# Motion_sensor.net
KiCad netlist of a schematic drawn in Altium Designer
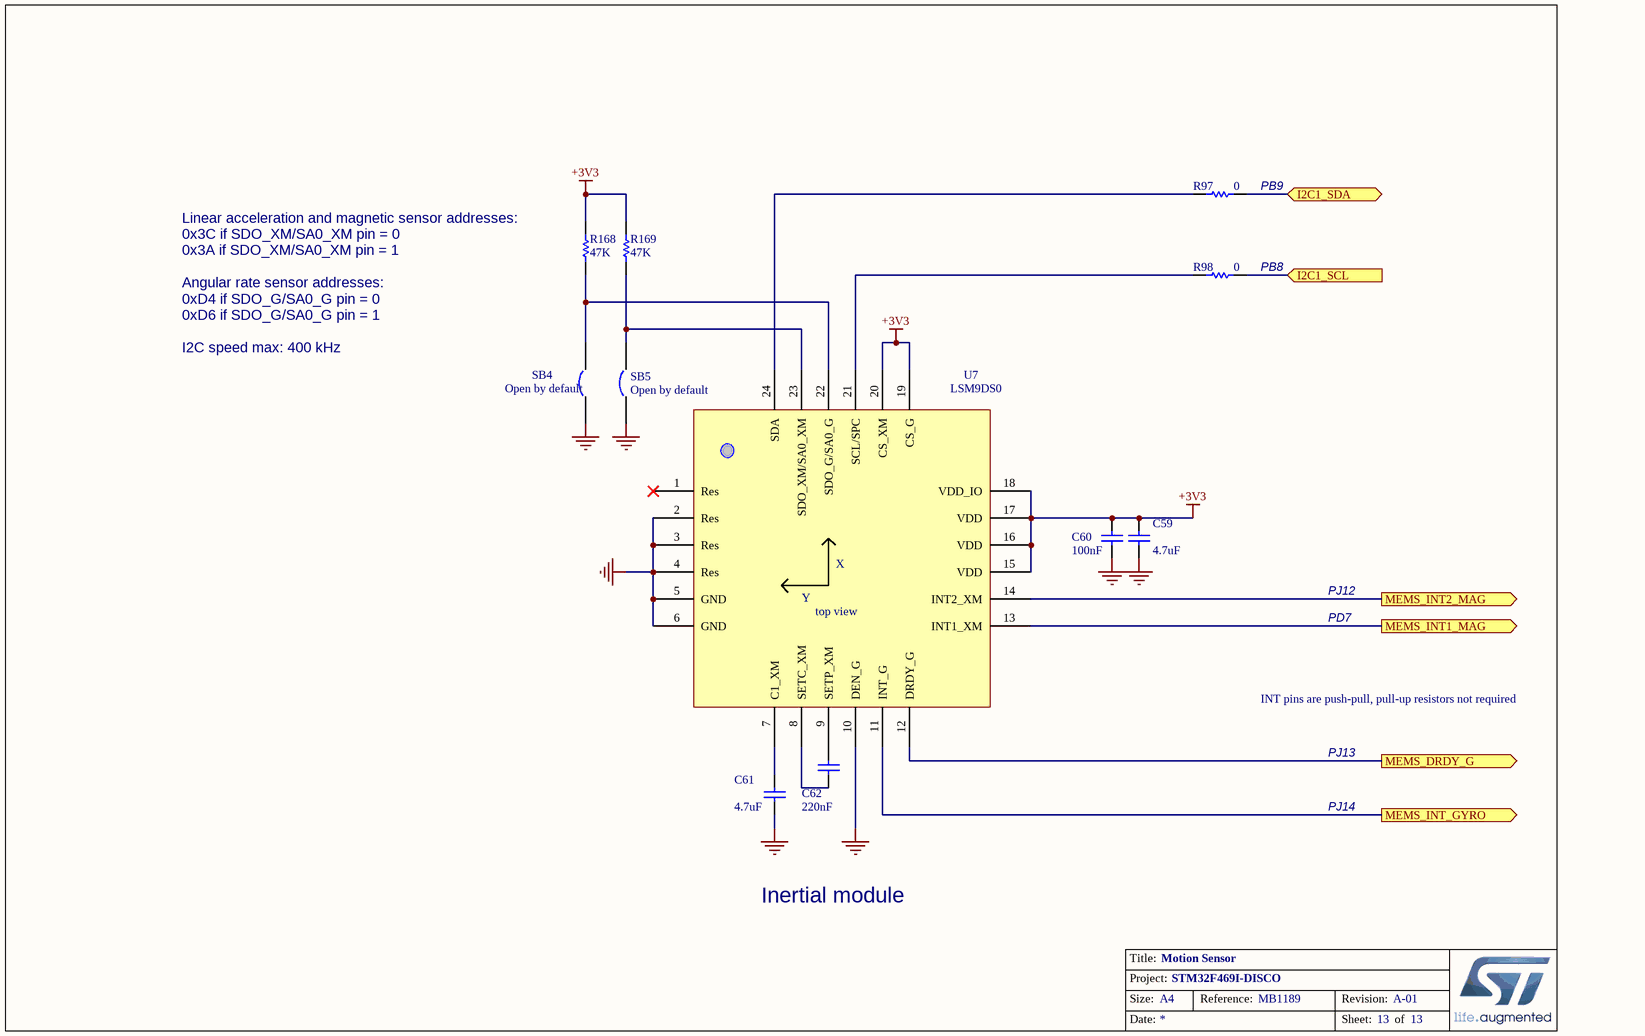
[diagram p0: Motion_sensor.SchDoc]

(export (version "E")
  (design (tool "Eeschema 10.0.6"))
  (components
    (comp (ref "C59")
      (value "4.7uF")
      (footprint "0603C")
      (description "Capacitor")
      (fields (field (name "PUBLISHER") "Altium Limited"))
      (libsource (lib "Miscellaneous Devices") (part "Cap"))
    )
    (comp (ref "C60")
      (value "100nF")
      (footprint "0402C")
      (description "Capacitor")
      (fields (field (name "PUBLISHER") "Altium Limited"))
      (libsource (lib "Miscellaneous Devices") (part "CAP"))
    )
    (comp (ref "C61")
      (value "4.7uF")
      (footprint "0603C")
      (description "Capacitor")
      (fields (field (name "PUBLISHER") "Altium Limited"))
      (libsource (lib "Miscellaneous Devices") (part "Cap"))
    )
    (comp (ref "C62")
      (value "220nF")
      (footprint "0603C")
      (description "Capacitor")
      (fields (field (name "PUBLISHER") "Altium Limited"))
      (libsource (lib "Miscellaneous Devices") (part "CAP"))
    )
    (comp (ref "R97")
      (value "0")
      (footprint "0603R")
      (description "Resistor")
      (fields (field (name "PUBLISHER") "Altium Limited"))
      (libsource (lib "Miscellaneous Devices") (part "Res1"))
    )
    (comp (ref "R98")
      (value "0")
      (footprint "0603R")
      (description "Resistor")
      (fields (field (name "PUBLISHER") "Altium Limited"))
      (libsource (lib "Miscellaneous Devices") (part "Res1"))
    )
    (comp (ref "R168")
      (value "47K")
      (footprint "0603R")
      (description "Resistor")
      (fields (field (name "PUBLISHER") "Altium Limited"))
      (libsource (lib "Miscellaneous Devices") (part "res1"))
    )
    (comp (ref "R169")
      (value "47K")
      (footprint "0603R")
      (description "Resistor")
      (fields (field (name "PUBLISHER") "Altium Limited"))
      (libsource (lib "Miscellaneous Devices") (part "res1"))
    )
    (comp (ref "SB4")
      (value "Open by default")
      (footprint "SB_0603")
      (description "Circuit Breaker")
      (fields (field (name "PUBLISHER") "Altium Limited"))
      (libsource (lib "Miscellaneous Devices") (part "Circuit Breaker"))
    )
    (comp (ref "SB5")
      (value "Open by default")
      (footprint "SB_0603")
      (description "Circuit Breaker")
      (fields (field (name "PUBLISHER") "Altium Limited"))
      (libsource (lib "Miscellaneous Devices") (part "Circuit Breaker"))
    )
    (comp (ref "U7")
      (value "LSM9DS0")
      (footprint "LGA-24")
      (description "inertial module")
      (libsource (lib "Almos") (part "LSM9DS0"))
    )
  )
  (nets
    (net (code "1") (name "+3V3") (class "Default")
      (node (ref "C59") (pin "1") (pinfunction "1_1") (pintype "passive"))
      (node (ref "C60") (pin "1") (pinfunction "1_1") (pintype "passive"))
      (node (ref "R168") (pin "1") (pinfunction "1_1") (pintype "passive"))
      (node (ref "R169") (pin "1") (pinfunction "1_1") (pintype "passive"))
      (node (ref "U7") (pin "15") (pinfunction "VDD_15") (pintype "passive"))
      (node (ref "U7") (pin "16") (pinfunction "VDD_16") (pintype "passive"))
      (node (ref "U7") (pin "17") (pinfunction "VDD_17") (pintype "passive"))
      (node (ref "U7") (pin "18") (pinfunction "VDD_IO_18") (pintype "passive"))
      (node (ref "U7") (pin "19") (pinfunction "CS_G_19") (pintype "passive"))
      (node (ref "U7") (pin "20") (pinfunction "CS_XM_20") (pintype "passive"))
    )
    (net (code "2") (name "/I2C1_SCL") (class "Default")
      (node (ref "R98") (pin "1") (pinfunction "1_1") (pintype "passive"))
    )
    (net (code "3") (name "/I2C1_SDA") (class "Default")
      (node (ref "R97") (pin "1") (pinfunction "1_1") (pintype "passive"))
    )
    (net (code "4") (name "/MEMS_DRDY_G") (class "Default")
      (node (ref "U7") (pin "12") (pinfunction "DRDY_G_12") (pintype "passive"))
    )
    (net (code "5") (name "/MEMS_INT1_MAG") (class "Default")
      (node (ref "U7") (pin "13") (pinfunction "INT1_XM_13") (pintype "passive"))
    )
    (net (code "6") (name "/MEMS_INT2_MAG") (class "Default")
      (node (ref "U7") (pin "14") (pinfunction "INT2_XM_14") (pintype "passive"))
    )
    (net (code "7") (name "/MEMS_INT_GYRO") (class "Default")
      (node (ref "U7") (pin "11") (pinfunction "INT_G_11") (pintype "passive"))
    )
    (net (code "8") (name "GND") (class "Default")
      (node (ref "C59") (pin "2") (pinfunction "2_2") (pintype "passive"))
      (node (ref "C60") (pin "2") (pinfunction "2_2") (pintype "passive"))
      (node (ref "C61") (pin "2") (pinfunction "2_2") (pintype "passive"))
      (node (ref "SB4") (pin "1") (pinfunction "1_1") (pintype "passive"))
      (node (ref "SB5") (pin "1") (pinfunction "1_1") (pintype "passive"))
      (node (ref "U7") (pin "10") (pinfunction "DEN_G_10") (pintype "passive"))
      (node (ref "U7") (pin "2") (pinfunction "Res_2") (pintype "passive"))
      (node (ref "U7") (pin "3") (pinfunction "Res_3") (pintype "passive"))
      (node (ref "U7") (pin "4") (pinfunction "Res_4") (pintype "passive"))
      (node (ref "U7") (pin "5") (pinfunction "GND_5") (pintype "passive"))
      (node (ref "U7") (pin "6") (pinfunction "GND_6") (pintype "passive"))
    )
    (net (code "9") (name "Net-(U7-C1_XM)") (class "Default")
      (node (ref "C61") (pin "1") (pinfunction "1_1") (pintype "passive"))
      (node (ref "U7") (pin "7") (pinfunction "C1_XM_7") (pintype "passive"))
    )
    (net (code "10") (name "Net-(U7-SCL{slash}SPC)") (class "Default")
      (node (ref "R98") (pin "2") (pinfunction "2_2") (pintype "passive"))
      (node (ref "U7") (pin "21") (pinfunction "SCL/SPC_21") (pintype "passive"))
    )
    (net (code "11") (name "Net-(U7-SDA)") (class "Default")
      (node (ref "R97") (pin "2") (pinfunction "2_2") (pintype "passive"))
      (node (ref "U7") (pin "24") (pinfunction "SDA_24") (pintype "passive"))
    )
    (net (code "12") (name "Net-(U7-SDO_G{slash}SA0_G)") (class "Default")
      (node (ref "R168") (pin "2") (pinfunction "2_2") (pintype "passive"))
      (node (ref "SB4") (pin "2") (pinfunction "2_2") (pintype "passive"))
      (node (ref "U7") (pin "22") (pinfunction "SDO_G/SA0_G_22") (pintype "passive"))
    )
    (net (code "13") (name "Net-(U7-SDO_XM{slash}SA0_XM)") (class "Default")
      (node (ref "R169") (pin "2") (pinfunction "2_2") (pintype "passive"))
      (node (ref "SB5") (pin "2") (pinfunction "2_2") (pintype "passive"))
      (node (ref "U7") (pin "23") (pinfunction "SDO_XM/SA0_XM_23") (pintype "passive"))
    )
    (net (code "14") (name "Net-(U7-SETC_XM)") (class "Default")
      (node (ref "C62") (pin "2") (pinfunction "2_2") (pintype "passive"))
      (node (ref "U7") (pin "8") (pinfunction "SETC_XM_8") (pintype "passive"))
    )
    (net (code "15") (name "Net-(U7-SETP_XM)") (class "Default")
      (node (ref "C62") (pin "1") (pinfunction "1_1") (pintype "passive"))
      (node (ref "U7") (pin "9") (pinfunction "SETP_XM_9") (pintype "passive"))
    )
    (net (code "16") (name "unconnected-(U7-Res-Pad1)") (class "Default")
      (node (ref "U7") (pin "1") (pinfunction "Res_1") (pintype "passive+no_connect"))
    )
  )
)
